# CONN.net
KiCad netlist of a schematic drawn in Altium Designer
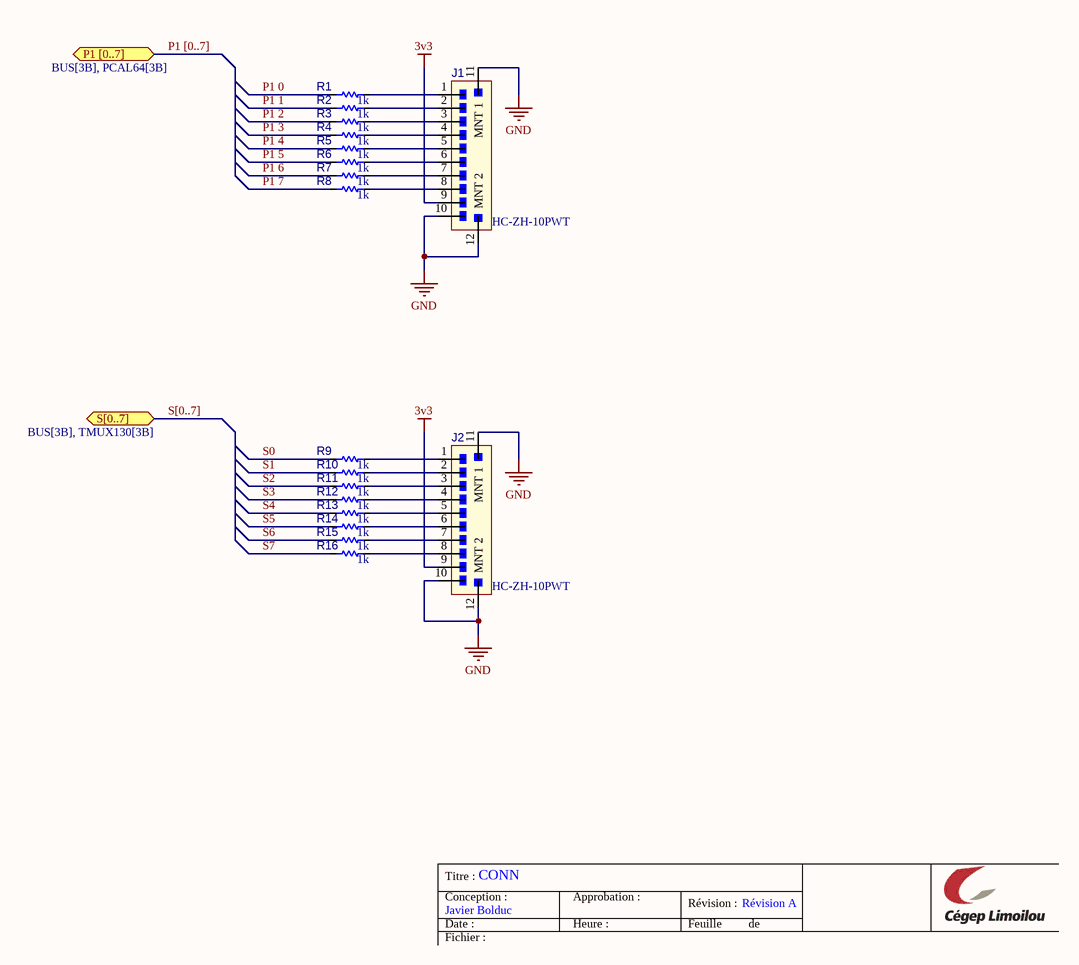
[diagram p0: CONN.schdoc]

(export (version "E")
  (design (tool "Eeschema 10.0.6"))
  (components
    (comp (ref "J1")
      (value "HC-ZH-10PWT")
      (footprint "J_S10B-ZR-SM4")
      (description "CONN wire to board SMT R/A 10POS 1.5mm")
      (libsource (lib "TEP-AltiumLib-Connectors") (part "CONN-1MM5-01X10-S10B-H-SMT"))
    )
    (comp (ref "J2")
      (value "HC-ZH-10PWT")
      (footprint "J_S10B-ZR-SM4")
      (description "CONN wire to board SMT R/A 10POS 1.5mm")
      (libsource (lib "TEP-AltiumLib-Connectors") (part "CONN-1MM5-01X10-S10B-H-SMT"))
    )
    (comp (ref "R1")
      (value "1k")
      (footprint "R_1608[0603]")
      (description "Resistor type 1")
      (fields (field (name "TOLERANCE") "1%") (field (name "Comment") "Res 1k 1% 0603"))
      (libsource (lib "TEP-AltiumLib-Passives-RLC") (part "resistor"))
    )
    (comp (ref "R2")
      (value "1k")
      (footprint "R_1608[0603]")
      (description "Resistor type 1")
      (fields (field (name "TOLERANCE") "1%") (field (name "Comment") "Res 1k 1% 0603"))
      (libsource (lib "TEP-AltiumLib-Passives-RLC") (part "resistor"))
    )
    (comp (ref "R3")
      (value "1k")
      (footprint "R_1608[0603]")
      (description "Resistor type 1")
      (fields (field (name "TOLERANCE") "1%") (field (name "Comment") "Res 1k 1% 0603"))
      (libsource (lib "TEP-AltiumLib-Passives-RLC") (part "resistor"))
    )
    (comp (ref "R4")
      (value "1k")
      (footprint "R_1608[0603]")
      (description "Resistor type 1")
      (fields (field (name "TOLERANCE") "1%") (field (name "Comment") "Res 1k 1% 0603"))
      (libsource (lib "TEP-AltiumLib-Passives-RLC") (part "resistor"))
    )
    (comp (ref "R5")
      (value "1k")
      (footprint "R_1608[0603]")
      (description "Resistor type 1")
      (fields (field (name "TOLERANCE") "1%") (field (name "Comment") "Res 1k 1% 0603"))
      (libsource (lib "TEP-AltiumLib-Passives-RLC") (part "resistor"))
    )
    (comp (ref "R6")
      (value "1k")
      (footprint "R_1608[0603]")
      (description "Resistor type 1")
      (fields (field (name "TOLERANCE") "1%") (field (name "Comment") "Res 1k 1% 0603"))
      (libsource (lib "TEP-AltiumLib-Passives-RLC") (part "resistor"))
    )
    (comp (ref "R7")
      (value "1k")
      (footprint "R_1608[0603]")
      (description "Resistor type 1")
      (fields (field (name "TOLERANCE") "1%") (field (name "Comment") "Res 1k 1% 0603"))
      (libsource (lib "TEP-AltiumLib-Passives-RLC") (part "resistor"))
    )
    (comp (ref "R8")
      (value "1k")
      (footprint "R_1608[0603]")
      (description "Resistor type 1")
      (fields (field (name "TOLERANCE") "1%") (field (name "Comment") "Res 1k 1% 0603"))
      (libsource (lib "TEP-AltiumLib-Passives-RLC") (part "resistor"))
    )
    (comp (ref "R9")
      (value "1k")
      (footprint "R_1608[0603]")
      (description "Resistor type 1")
      (fields (field (name "TOLERANCE") "1%") (field (name "Comment") "Res 1k 1% 0603"))
      (libsource (lib "TEP-AltiumLib-Passives-RLC") (part "resistor"))
    )
    (comp (ref "R10")
      (value "1k")
      (footprint "R_1608[0603]")
      (description "Resistor type 1")
      (fields (field (name "TOLERANCE") "1%") (field (name "Comment") "Res 1k 1% 0603"))
      (libsource (lib "TEP-AltiumLib-Passives-RLC") (part "resistor"))
    )
    (comp (ref "R11")
      (value "1k")
      (footprint "R_1608[0603]")
      (description "Resistor type 1")
      (fields (field (name "TOLERANCE") "1%") (field (name "Comment") "Res 1k 1% 0603"))
      (libsource (lib "TEP-AltiumLib-Passives-RLC") (part "resistor"))
    )
    (comp (ref "R12")
      (value "1k")
      (footprint "R_1608[0603]")
      (description "Resistor type 1")
      (fields (field (name "TOLERANCE") "1%") (field (name "Comment") "Res 1k 1% 0603"))
      (libsource (lib "TEP-AltiumLib-Passives-RLC") (part "resistor"))
    )
    (comp (ref "R13")
      (value "1k")
      (footprint "R_1608[0603]")
      (description "Resistor type 1")
      (fields (field (name "TOLERANCE") "1%") (field (name "Comment") "Res 1k 1% 0603"))
      (libsource (lib "TEP-AltiumLib-Passives-RLC") (part "resistor"))
    )
    (comp (ref "R14")
      (value "1k")
      (footprint "R_1608[0603]")
      (description "Resistor type 1")
      (fields (field (name "TOLERANCE") "1%") (field (name "Comment") "Res 1k 1% 0603"))
      (libsource (lib "TEP-AltiumLib-Passives-RLC") (part "resistor"))
    )
    (comp (ref "R15")
      (value "1k")
      (footprint "R_1608[0603]")
      (description "Resistor type 1")
      (fields (field (name "TOLERANCE") "1%") (field (name "Comment") "Res 1k 1% 0603"))
      (libsource (lib "TEP-AltiumLib-Passives-RLC") (part "resistor"))
    )
    (comp (ref "R16")
      (value "1k")
      (footprint "R_1608[0603]")
      (description "Resistor type 1")
      (fields (field (name "TOLERANCE") "1%") (field (name "Comment") "Res 1k 1% 0603"))
      (libsource (lib "TEP-AltiumLib-Passives-RLC") (part "resistor"))
    )
  )
  (nets
    (net (code "1") (name "/P1 0") (class "Default")
      (node (ref "R1") (pin "2") (pinfunction "2_2") (pintype "passive"))
    )
    (net (code "2") (name "/P1 1") (class "Default")
      (node (ref "R2") (pin "2") (pinfunction "2_2") (pintype "passive"))
    )
    (net (code "3") (name "/P1 2") (class "Default")
      (node (ref "R3") (pin "2") (pinfunction "2_2") (pintype "passive"))
    )
    (net (code "4") (name "/P1 3") (class "Default")
      (node (ref "R4") (pin "2") (pinfunction "2_2") (pintype "passive"))
    )
    (net (code "5") (name "/P1 4") (class "Default")
      (node (ref "R5") (pin "2") (pinfunction "2_2") (pintype "passive"))
    )
    (net (code "6") (name "/P1 5") (class "Default")
      (node (ref "R6") (pin "2") (pinfunction "2_2") (pintype "passive"))
    )
    (net (code "7") (name "/P1 6") (class "Default")
      (node (ref "R7") (pin "2") (pinfunction "2_2") (pintype "passive"))
    )
    (net (code "8") (name "/P1 7") (class "Default")
      (node (ref "R8") (pin "2") (pinfunction "2_2") (pintype "passive"))
    )
    (net (code "9") (name "/S0") (class "Default")
      (node (ref "R9") (pin "2") (pinfunction "2_2") (pintype "passive"))
    )
    (net (code "10") (name "/S1") (class "Default")
      (node (ref "R10") (pin "2") (pinfunction "2_2") (pintype "passive"))
    )
    (net (code "11") (name "/S2") (class "Default")
      (node (ref "R11") (pin "2") (pinfunction "2_2") (pintype "passive"))
    )
    (net (code "12") (name "/S3") (class "Default")
      (node (ref "R12") (pin "2") (pinfunction "2_2") (pintype "passive"))
    )
    (net (code "13") (name "/S4") (class "Default")
      (node (ref "R13") (pin "2") (pinfunction "2_2") (pintype "passive"))
    )
    (net (code "14") (name "/S5") (class "Default")
      (node (ref "R14") (pin "2") (pinfunction "2_2") (pintype "passive"))
    )
    (net (code "15") (name "/S6") (class "Default")
      (node (ref "R15") (pin "2") (pinfunction "2_2") (pintype "passive"))
    )
    (net (code "16") (name "/S7") (class "Default")
      (node (ref "R16") (pin "2") (pinfunction "2_2") (pintype "passive"))
    )
    (net (code "19") (name "3v3") (class "Default")
      (node (ref "J1") (pin "9") (pinfunction "9_9") (pintype "passive"))
      (node (ref "J2") (pin "9") (pinfunction "9_9") (pintype "passive"))
    )
    (net (code "20") (name "GND") (class "Default")
      (node (ref "J1") (pin "10") (pinfunction "10_10") (pintype "passive"))
      (node (ref "J1") (pin "11") (pinfunction "MNT_1_11") (pintype "passive"))
      (node (ref "J1") (pin "12") (pinfunction "MNT_2_12") (pintype "passive"))
      (node (ref "J2") (pin "10") (pinfunction "10_10") (pintype "passive"))
      (node (ref "J2") (pin "11") (pinfunction "MNT_1_11") (pintype "passive"))
      (node (ref "J2") (pin "12") (pinfunction "MNT_2_12") (pintype "passive"))
    )
    (net (code "21") (name "Net-(J1-Pad1)") (class "Default")
      (node (ref "J1") (pin "1") (pinfunction "1_1") (pintype "passive"))
      (node (ref "R1") (pin "1") (pinfunction "1_1") (pintype "passive"))
    )
    (net (code "22") (name "Net-(J1-Pad2)") (class "Default")
      (node (ref "J1") (pin "2") (pinfunction "2_2") (pintype "passive"))
      (node (ref "R2") (pin "1") (pinfunction "1_1") (pintype "passive"))
    )
    (net (code "23") (name "Net-(J1-Pad3)") (class "Default")
      (node (ref "J1") (pin "3") (pinfunction "3_3") (pintype "passive"))
      (node (ref "R3") (pin "1") (pinfunction "1_1") (pintype "passive"))
    )
    (net (code "24") (name "Net-(J1-Pad4)") (class "Default")
      (node (ref "J1") (pin "4") (pinfunction "4_4") (pintype "passive"))
      (node (ref "R4") (pin "1") (pinfunction "1_1") (pintype "passive"))
    )
    (net (code "25") (name "Net-(J1-Pad5)") (class "Default")
      (node (ref "J1") (pin "5") (pinfunction "5_5") (pintype "passive"))
      (node (ref "R5") (pin "1") (pinfunction "1_1") (pintype "passive"))
    )
    (net (code "26") (name "Net-(J1-Pad6)") (class "Default")
      (node (ref "J1") (pin "6") (pinfunction "6_6") (pintype "passive"))
      (node (ref "R6") (pin "1") (pinfunction "1_1") (pintype "passive"))
    )
    (net (code "27") (name "Net-(J1-Pad7)") (class "Default")
      (node (ref "J1") (pin "7") (pinfunction "7_7") (pintype "passive"))
      (node (ref "R7") (pin "1") (pinfunction "1_1") (pintype "passive"))
    )
    (net (code "28") (name "Net-(J1-Pad8)") (class "Default")
      (node (ref "J1") (pin "8") (pinfunction "8_8") (pintype "passive"))
      (node (ref "R8") (pin "1") (pinfunction "1_1") (pintype "passive"))
    )
    (net (code "29") (name "Net-(J2-Pad1)") (class "Default")
      (node (ref "J2") (pin "1") (pinfunction "1_1") (pintype "passive"))
      (node (ref "R9") (pin "1") (pinfunction "1_1") (pintype "passive"))
    )
    (net (code "30") (name "Net-(J2-Pad2)") (class "Default")
      (node (ref "J2") (pin "2") (pinfunction "2_2") (pintype "passive"))
      (node (ref "R10") (pin "1") (pinfunction "1_1") (pintype "passive"))
    )
    (net (code "31") (name "Net-(J2-Pad3)") (class "Default")
      (node (ref "J2") (pin "3") (pinfunction "3_3") (pintype "passive"))
      (node (ref "R11") (pin "1") (pinfunction "1_1") (pintype "passive"))
    )
    (net (code "32") (name "Net-(J2-Pad4)") (class "Default")
      (node (ref "J2") (pin "4") (pinfunction "4_4") (pintype "passive"))
      (node (ref "R12") (pin "1") (pinfunction "1_1") (pintype "passive"))
    )
    (net (code "33") (name "Net-(J2-Pad5)") (class "Default")
      (node (ref "J2") (pin "5") (pinfunction "5_5") (pintype "passive"))
      (node (ref "R13") (pin "1") (pinfunction "1_1") (pintype "passive"))
    )
    (net (code "34") (name "Net-(J2-Pad6)") (class "Default")
      (node (ref "J2") (pin "6") (pinfunction "6_6") (pintype "passive"))
      (node (ref "R14") (pin "1") (pinfunction "1_1") (pintype "passive"))
    )
    (net (code "35") (name "Net-(J2-Pad7)") (class "Default")
      (node (ref "J2") (pin "7") (pinfunction "7_7") (pintype "passive"))
      (node (ref "R15") (pin "1") (pinfunction "1_1") (pintype "passive"))
    )
    (net (code "36") (name "Net-(J2-Pad8)") (class "Default")
      (node (ref "J2") (pin "8") (pinfunction "8_8") (pintype "passive"))
      (node (ref "R16") (pin "1") (pinfunction "1_1") (pintype "passive"))
    )
  )
)
